# babylight.net
KiCad netlist of a schematic drawn in EAGLE
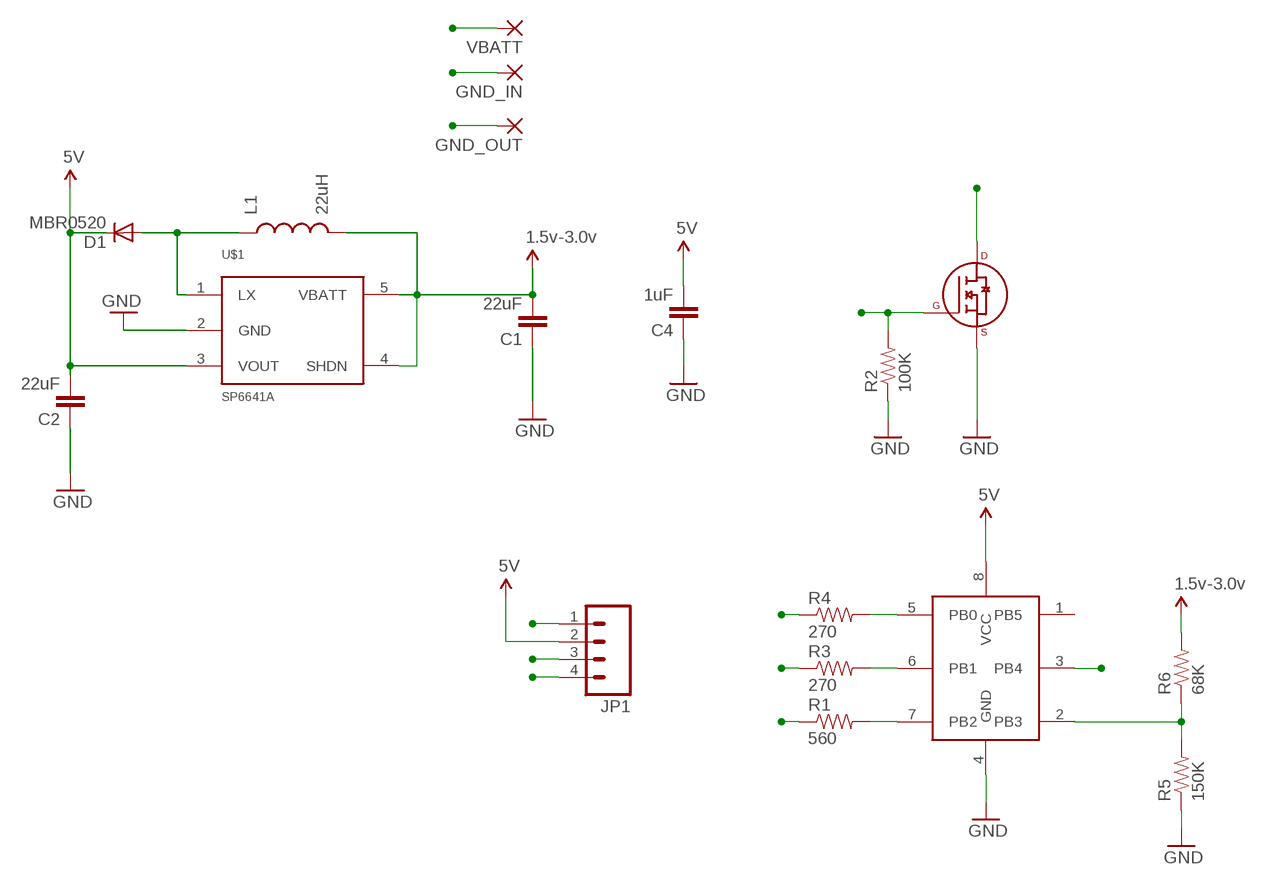
[diagram p0: schematic, sheet 1]

(export (version "E")
  (design (tool "Eeschema 10.0.6"))
  (components
    (comp (ref "C1")
      (value "22uF")
      (footprint "eagle-import:0603-CAP")
      (libsource (lib "eagle-import") (part "CAP0603-CAP"))
    )
    (comp (ref "C2")
      (value "22uF")
      (footprint "eagle-import:0603-CAP")
      (libsource (lib "eagle-import") (part "CAP0603-CAP"))
    )
    (comp (ref "C4")
      (value "1uF")
      (footprint "eagle-import:0603-CAP")
      (libsource (lib "eagle-import") (part "CAP0603-CAP"))
    )
    (comp (ref "D1")
      (value "MBR0520")
      (footprint "eagle-import:SOD123")
      (libsource (lib "eagle-import") (part "MBR0520LT"))
    )
    (comp (ref "GND_IN")
      (value "WIREPAD2,54/1,0")
      (footprint "eagle-import:2,54_1,0")
      (libsource (lib "eagle-import") (part "WIREPAD2,54/1,0"))
    )
    (comp (ref "GND_OUT")
      (value "WIREPAD2,54/1,0")
      (footprint "eagle-import:2,54_1,0")
      (libsource (lib "eagle-import") (part "WIREPAD2,54/1,0"))
    )
    (comp (ref "JP1")
      (value "M04LONGPADS")
      (footprint "eagle-import:1X04_LONGPADS")
      (libsource (lib "eagle-import") (part "M04LONGPADS"))
    )
    (comp (ref "L1")
      (value "22uH")
      (footprint "eagle-import:CR54")
      (libsource (lib "eagle-import") (part "INDUCTORCR54"))
    )
    (comp (ref "R1")
      (value "560")
      (footprint "eagle-import:0805")
      (libsource (lib "eagle-import") (part "RESISTOR0805-RES"))
    )
    (comp (ref "R2")
      (value "100K")
      (footprint "eagle-import:0805")
      (libsource (lib "eagle-import") (part "RESISTOR0805-RES"))
    )
    (comp (ref "R3")
      (value "270")
      (footprint "eagle-import:0805")
      (libsource (lib "eagle-import") (part "RESISTOR0805-RES"))
    )
    (comp (ref "R4")
      (value "270")
      (footprint "eagle-import:0805")
      (libsource (lib "eagle-import") (part "RESISTOR0805-RES"))
    )
    (comp (ref "R5")
      (value "150K")
      (footprint "eagle-import:0603-RES")
      (libsource (lib "eagle-import") (part "RESISTOR0603-RES"))
    )
    (comp (ref "R6")
      (value "68K")
      (footprint "eagle-import:0603-RES")
      (libsource (lib "eagle-import") (part "RESISTOR0603-RES"))
    )
    (comp (ref "U$1")
      (value "SP6641A")
      (footprint "eagle-import:SOT23-5")
      (libsource (lib "eagle-import") (part "SP6641SP6641A/B"))
    )
    (comp (ref "U$2")
      (value "ATTINY13")
      (footprint "eagle-import:WSOIC-8")
      (libsource (lib "eagle-import") (part "ATTINY13"))
    )
    (comp (ref "U$7")
      (value "FQT13N06LTF")
      (footprint "eagle-import:SOT-223")
      (libsource (lib "eagle-import") (part "FQT13N06LTF"))
    )
    (comp (ref "VBATT")
      (value "WIREPAD2,54/1,0")
      (footprint "eagle-import:2,54_1,0")
      (libsource (lib "eagle-import") (part "WIREPAD2,54/1,0"))
    )
  )
  (nets
    (net (code "1") (name "/BLU") (class "Default")
      (node (ref "JP1") (pin "4") (pinfunction "4_4") (pintype "passive"))
      (node (ref "R4") (pin "1") (pinfunction "1_1") (pintype "passive"))
    )
    (net (code "2") (name "/GND_OUT") (class "Default")
      (node (ref "GND_OUT") (pin "1") (pinfunction "P_1") (pintype "passive"))
      (node (ref "U$7") (pin "4") (pinfunction "D_4") (pintype "bidirectional"))
    )
    (net (code "3") (name "/GRN") (class "Default")
      (node (ref "JP1") (pin "3") (pinfunction "3_3") (pintype "passive"))
      (node (ref "R3") (pin "1") (pinfunction "1_1") (pintype "passive"))
    )
    (net (code "4") (name "/RED") (class "Default")
      (node (ref "JP1") (pin "1") (pinfunction "1_1") (pintype "passive"))
      (node (ref "R1") (pin "1") (pinfunction "1_1") (pintype "passive"))
    )
    (net (code "5") (name "/SW") (class "Default")
      (node (ref "R2") (pin "2") (pinfunction "2_2") (pintype "passive"))
      (node (ref "U$2") (pin "3") (pinfunction "PB4_3") (pintype "bidirectional"))
      (node (ref "U$7") (pin "1") (pinfunction "G_1") (pintype "bidirectional"))
    )
    (net (code "6") (name "1.5v-3.0v") (class "Default")
      (node (ref "C1") (pin "2") (pinfunction "2_2") (pintype "passive"))
      (node (ref "L1") (pin "P$2") (pinfunction "2_P$2") (pintype "passive"))
      (node (ref "R6") (pin "2") (pinfunction "2_2") (pintype "passive"))
      (node (ref "U$1") (pin "4") (pinfunction "SHDN_4") (pintype "bidirectional"))
      (node (ref "U$1") (pin "5") (pinfunction "VBATT_5") (pintype "bidirectional"))
      (node (ref "VBATT") (pin "1") (pinfunction "P_1") (pintype "passive"))
    )
    (net (code "7") (name "5V") (class "Default")
      (node (ref "C2") (pin "2") (pinfunction "2_2") (pintype "passive"))
      (node (ref "C4") (pin "2") (pinfunction "2_2") (pintype "passive"))
      (node (ref "D1") (pin "C") (pinfunction "C_C") (pintype "passive"))
      (node (ref "JP1") (pin "2") (pinfunction "2_2") (pintype "passive"))
      (node (ref "U$1") (pin "3") (pinfunction "VOUT_3") (pintype "bidirectional"))
      (node (ref "U$2") (pin "8") (pinfunction "VCC_8") (pintype "bidirectional"))
    )
    (net (code "8") (name "GND") (class "Default")
      (node (ref "C1") (pin "1") (pinfunction "1_1") (pintype "passive"))
      (node (ref "C2") (pin "1") (pinfunction "1_1") (pintype "passive"))
      (node (ref "C4") (pin "1") (pinfunction "1_1") (pintype "passive"))
      (node (ref "GND_IN") (pin "1") (pinfunction "P_1") (pintype "passive"))
      (node (ref "R2") (pin "1") (pinfunction "1_1") (pintype "passive"))
      (node (ref "R5") (pin "1") (pinfunction "1_1") (pintype "passive"))
      (node (ref "U$1") (pin "2") (pinfunction "GND_2") (pintype "bidirectional"))
      (node (ref "U$2") (pin "4") (pinfunction "GND_4") (pintype "bidirectional"))
      (node (ref "U$7") (pin "3") (pinfunction "S_3") (pintype "bidirectional"))
    )
    (net (code "9") (name "Net-(L1-1)") (class "Default")
      (node (ref "D1") (pin "A") (pinfunction "A_A") (pintype "passive"))
      (node (ref "L1") (pin "P$1") (pinfunction "1_P$1") (pintype "passive"))
      (node (ref "U$1") (pin "1") (pinfunction "LX_1") (pintype "bidirectional"))
    )
    (net (code "10") (name "Net-(U$2-PB0)") (class "Default")
      (node (ref "R4") (pin "2") (pinfunction "2_2") (pintype "passive"))
      (node (ref "U$2") (pin "5") (pinfunction "PB0_5") (pintype "bidirectional"))
    )
    (net (code "11") (name "Net-(U$2-PB1)") (class "Default")
      (node (ref "R3") (pin "2") (pinfunction "2_2") (pintype "passive"))
      (node (ref "U$2") (pin "6") (pinfunction "PB1_6") (pintype "bidirectional"))
    )
    (net (code "12") (name "Net-(U$2-PB2)") (class "Default")
      (node (ref "R1") (pin "2") (pinfunction "2_2") (pintype "passive"))
      (node (ref "U$2") (pin "7") (pinfunction "PB2_7") (pintype "bidirectional"))
    )
    (net (code "13") (name "Net-(U$2-PB3)") (class "Default")
      (node (ref "R5") (pin "2") (pinfunction "2_2") (pintype "passive"))
      (node (ref "R6") (pin "1") (pinfunction "1_1") (pintype "passive"))
      (node (ref "U$2") (pin "2") (pinfunction "PB3_2") (pintype "bidirectional"))
    )
    (net (code "14") (name "unconnected-(U$2-PB5-Pad1)") (class "Default")
      (node (ref "U$2") (pin "1") (pinfunction "PB5_1") (pintype "bidirectional"))
    )
  )
)
